# Teensy3_based_M_M_board.net
KiCad netlist of a schematic drawn in EAGLE
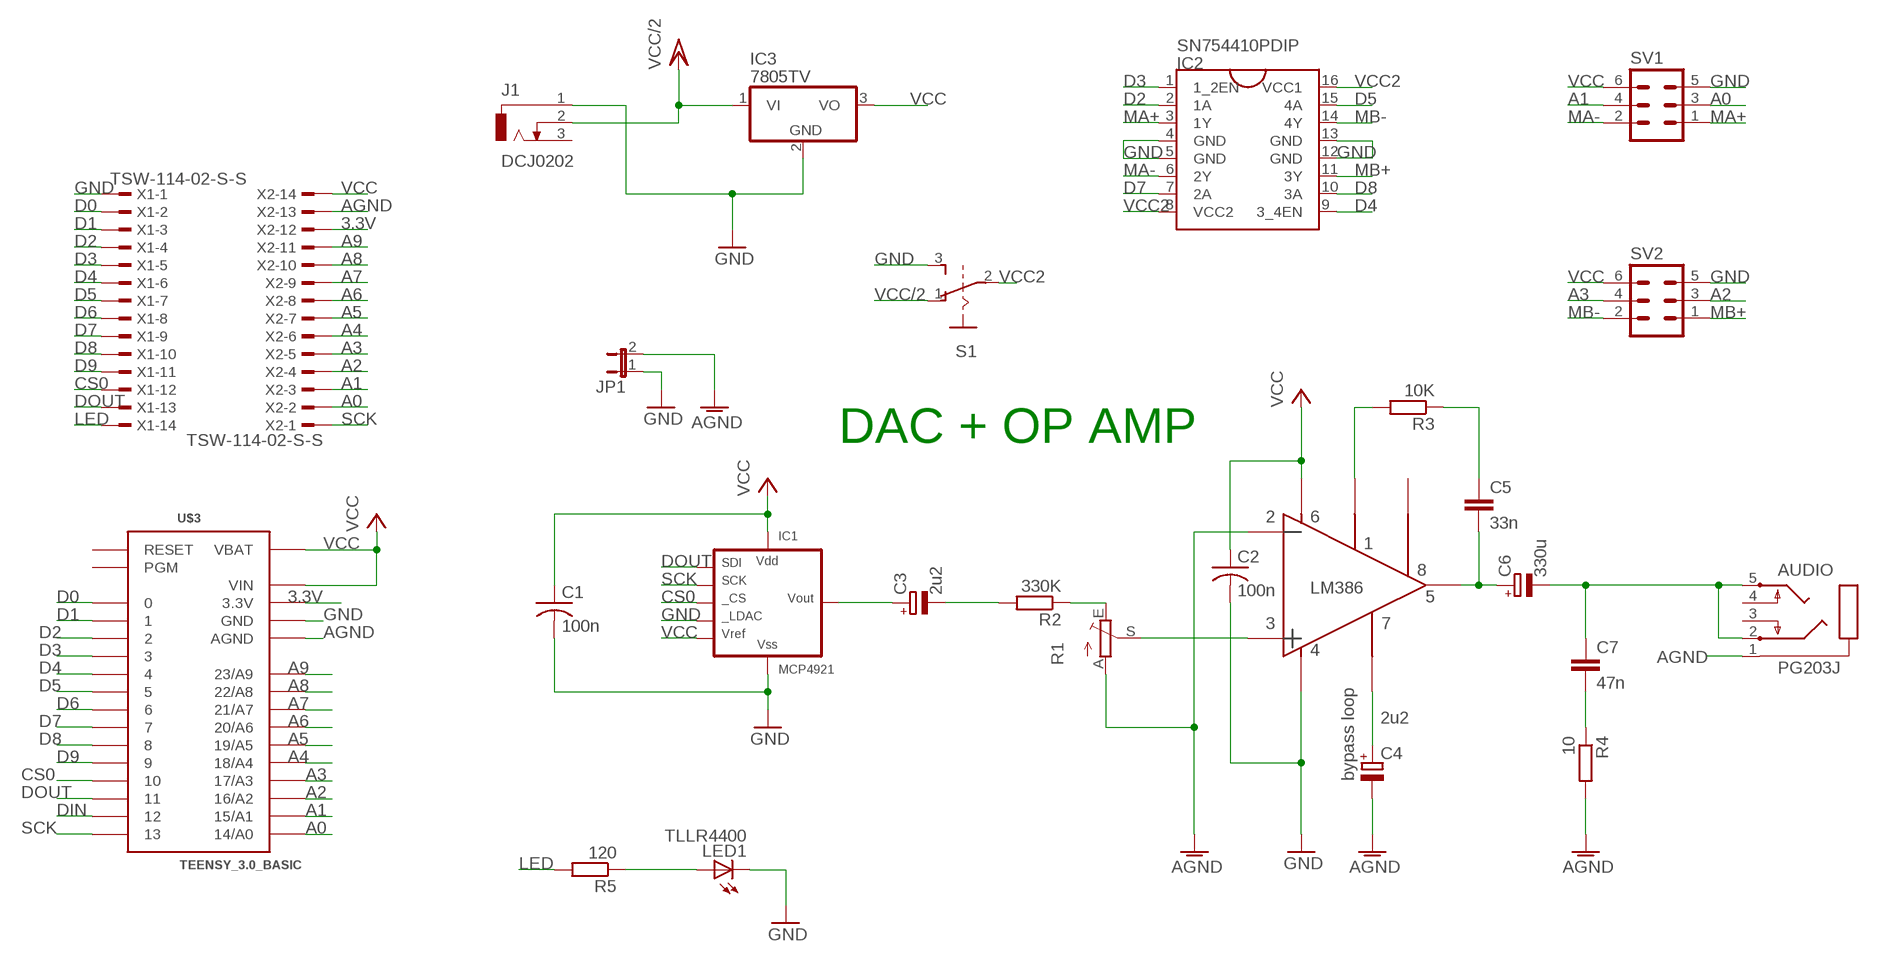
[diagram p0: schematic, sheet 1]

(export (version "E")
  (design (tool "Eeschema 10.0.6"))
  (components
    (comp (ref "AUDIO")
      (value "PG203J")
      (footprint "eagle-import:PG203J")
      (libsource (lib "eagle-import") (part "PG203J"))
    )
    (comp (ref "C1")
      (value "100n")
      (footprint "eagle-import:C050-035X075")
      (libsource (lib "eagle-import") (part "C-US050-035X075"))
    )
    (comp (ref "C2")
      (value "100n")
      (footprint "eagle-import:C050-035X075")
      (libsource (lib "eagle-import") (part "C-US050-035X075"))
    )
    (comp (ref "C3")
      (value "2u2")
      (footprint "eagle-import:E2-5")
      (libsource (lib "eagle-import") (part "CPOL-EUE2-5"))
    )
    (comp (ref "C4")
      (value "2u2")
      (footprint "eagle-import:E2-5")
      (libsource (lib "eagle-import") (part "CPOL-EUE2-5"))
    )
    (comp (ref "C5")
      (value "33n")
      (footprint "eagle-import:C050-024X044")
      (libsource (lib "eagle-import") (part "C-EU050-024X044"))
    )
    (comp (ref "C6")
      (value "330u")
      (footprint "eagle-import:E2,5-7")
      (libsource (lib "eagle-import") (part "CPOL-EUE2.5-7"))
    )
    (comp (ref "C7")
      (value "47n")
      (footprint "eagle-import:C050-024X044")
      (libsource (lib "eagle-import") (part "C-EU050-024X044"))
    )
    (comp (ref "IC1")
      (value "MCP4921")
      (footprint "eagle-import:DIL8")
      (libsource (lib "eagle-import") (part "MCP4921P"))
    )
    (comp (ref "IC2")
      (value "SN754410PDIP")
      (footprint "eagle-import:DIL16")
      (libsource (lib "eagle-import") (part "SN754410PDIP"))
    )
    (comp (ref "IC3")
      (value "7805TV")
      (footprint "eagle-import:TO220V")
      (libsource (lib "eagle-import") (part "78TV05"))
    )
    (comp (ref "J1")
      (value "DCJ0202")
      (footprint "eagle-import:DCJ0202")
      (libsource (lib "eagle-import") (part "DCJ0202"))
    )
    (comp (ref "JP1")
      (value "JP1E")
      (footprint "eagle-import:JP1")
      (libsource (lib "eagle-import") (part "JP1E"))
    )
    (comp (ref "LED1")
      (value "TLLR4400")
      (footprint "eagle-import:LED3MM")
      (fields (field (name "MF") "VISHAY SEMICONDUCTOR"))
      (libsource (lib "eagle-import") (part "TLLR4400"))
    )
    (comp (ref "R1")
      (value "TRIM_EU-CA9V")
      (footprint "eagle-import:CA9V")
      (libsource (lib "eagle-import") (part "TRIM_EU-CA9V"))
    )
    (comp (ref "R2")
      (value "330K")
      (footprint "eagle-import:0207_10")
      (libsource (lib "eagle-import") (part "R-EU_0207/10"))
    )
    (comp (ref "R3")
      (value "10K")
      (footprint "eagle-import:0207_10")
      (libsource (lib "eagle-import") (part "R-EU_0207/10"))
    )
    (comp (ref "R4")
      (value "10")
      (footprint "eagle-import:0207_10")
      (libsource (lib "eagle-import") (part "R-EU_0207/10"))
    )
    (comp (ref "R5")
      (value "120")
      (footprint "eagle-import:0207_10")
      (libsource (lib "eagle-import") (part "R-EU_0207/10"))
    )
    (comp (ref "S1")
      (value "EG1218")
      (footprint "eagle-import:GF-126-0159")
      (libsource (lib "eagle-import") (part "EG1218"))
    )
    (comp (ref "SV1")
      (value "ML6")
      (footprint "eagle-import:ML6")
      (libsource (lib "eagle-import") (part "ML6"))
    )
    (comp (ref "SV2")
      (value "ML6")
      (footprint "eagle-import:ML6")
      (libsource (lib "eagle-import") (part "ML6"))
    )
    (comp (ref "U$2")
      (value "LM386")
      (footprint "eagle-import:LM386")
      (libsource (lib "eagle-import") (part "LM386OA"))
    )
    (comp (ref "U$3")
      (value "TEENSY_3.0_BASIC")
      (footprint "eagle-import:TEENSY_3.0_BASIC")
      (libsource (lib "eagle-import") (part "TEENSY_3.0_BASIC"))
    )
    (comp (ref "X1")
      (value "TSW-114-02-S-S")
      (footprint "eagle-import:TSW-114-02-S-S")
      (libsource (lib "eagle-import") (part "TSW-114-02-S-S"))
    )
    (comp (ref "X2")
      (value "TSW-114-02-S-S")
      (footprint "eagle-import:TSW-114-02-S-S")
      (libsource (lib "eagle-import") (part "TSW-114-02-S-S"))
    )
  )
  (nets
    (net (code "1") (name "/3.3V") (class "Default")
      (node (ref "U$3") (pin "3.3V") (pinfunction "3.3V_3.3V") (pintype "power_in"))
      (node (ref "U$3") (pin "3.3V1") (pinfunction "3.3V_3.3V1") (pintype "power_in"))
      (node (ref "X2") (pin "12") (pinfunction "1_12") (pintype "passive"))
    )
    (net (code "2") (name "/A0") (class "Default")
      (node (ref "SV1") (pin "3") (pinfunction "3_3") (pintype "passive"))
      (node (ref "U$3") (pin "14/A0") (pinfunction "14/A0_14/A0") (pintype "bidirectional"))
      (node (ref "X2") (pin "2") (pinfunction "1_2") (pintype "passive"))
    )
    (net (code "3") (name "/A1") (class "Default")
      (node (ref "SV1") (pin "4") (pinfunction "4_4") (pintype "passive"))
      (node (ref "U$3") (pin "15/A1") (pinfunction "15/A1_15/A1") (pintype "bidirectional"))
      (node (ref "X2") (pin "3") (pinfunction "1_3") (pintype "passive"))
    )
    (net (code "4") (name "/A2") (class "Default")
      (node (ref "SV2") (pin "3") (pinfunction "3_3") (pintype "passive"))
      (node (ref "U$3") (pin "16/A2") (pinfunction "16/A2_16/A2") (pintype "bidirectional"))
      (node (ref "X2") (pin "4") (pinfunction "1_4") (pintype "passive"))
    )
    (net (code "5") (name "/A3") (class "Default")
      (node (ref "SV2") (pin "4") (pinfunction "4_4") (pintype "passive"))
      (node (ref "U$3") (pin "17/A3") (pinfunction "17/A3_17/A3") (pintype "bidirectional"))
      (node (ref "X2") (pin "5") (pinfunction "1_5") (pintype "passive"))
    )
    (net (code "6") (name "/A4") (class "Default")
      (node (ref "U$3") (pin "18/A4") (pinfunction "18/A4_18/A4") (pintype "bidirectional"))
      (node (ref "X2") (pin "6") (pinfunction "1_6") (pintype "passive"))
    )
    (net (code "7") (name "/A5") (class "Default")
      (node (ref "U$3") (pin "19/A5") (pinfunction "19/A5_19/A5") (pintype "bidirectional"))
      (node (ref "X2") (pin "7") (pinfunction "1_7") (pintype "passive"))
    )
    (net (code "8") (name "/A6") (class "Default")
      (node (ref "U$3") (pin "20/A6") (pinfunction "20/A6_20/A6") (pintype "bidirectional"))
      (node (ref "X2") (pin "8") (pinfunction "1_8") (pintype "passive"))
    )
    (net (code "9") (name "/A7") (class "Default")
      (node (ref "U$3") (pin "21/A7") (pinfunction "21/A7_21/A7") (pintype "bidirectional"))
      (node (ref "X2") (pin "9") (pinfunction "1_9") (pintype "passive"))
    )
    (net (code "10") (name "/A8") (class "Default")
      (node (ref "U$3") (pin "22/A8") (pinfunction "22/A8_22/A8") (pintype "bidirectional"))
      (node (ref "X2") (pin "10") (pinfunction "1_10") (pintype "passive"))
    )
    (net (code "11") (name "/A9") (class "Default")
      (node (ref "U$3") (pin "23/A9") (pinfunction "23/A9_23/A9") (pintype "bidirectional"))
      (node (ref "X2") (pin "11") (pinfunction "1_11") (pintype "passive"))
    )
    (net (code "12") (name "/CS0") (class "Default")
      (node (ref "IC1") (pin "2") (pinfunction "CS_2") (pintype "input"))
      (node (ref "U$3") (pin "10") (pinfunction "10_10") (pintype "bidirectional"))
      (node (ref "X1") (pin "12") (pinfunction "1_12") (pintype "passive"))
    )
    (net (code "13") (name "/D0") (class "Default")
      (node (ref "U$3") (pin "0") (pinfunction "0_0") (pintype "bidirectional"))
      (node (ref "X1") (pin "2") (pinfunction "1_2") (pintype "passive"))
    )
    (net (code "14") (name "/D1") (class "Default")
      (node (ref "U$3") (pin "1") (pinfunction "1_1") (pintype "bidirectional"))
      (node (ref "X1") (pin "3") (pinfunction "1_3") (pintype "passive"))
    )
    (net (code "15") (name "/D2") (class "Default")
      (node (ref "IC2") (pin "2") (pinfunction "1A_2") (pintype "bidirectional"))
      (node (ref "U$3") (pin "2") (pinfunction "2_2") (pintype "bidirectional"))
      (node (ref "X1") (pin "4") (pinfunction "1_4") (pintype "passive"))
    )
    (net (code "16") (name "/D3") (class "Default")
      (node (ref "IC2") (pin "1") (pinfunction "1_2EN_1") (pintype "bidirectional"))
      (node (ref "U$3") (pin "3") (pinfunction "3_3") (pintype "bidirectional"))
      (node (ref "X1") (pin "5") (pinfunction "1_5") (pintype "passive"))
    )
    (net (code "17") (name "/D4") (class "Default")
      (node (ref "IC2") (pin "9") (pinfunction "3_4EN_9") (pintype "bidirectional"))
      (node (ref "U$3") (pin "4") (pinfunction "4_4") (pintype "bidirectional"))
      (node (ref "X1") (pin "6") (pinfunction "1_6") (pintype "passive"))
    )
    (net (code "18") (name "/D5") (class "Default")
      (node (ref "IC2") (pin "15") (pinfunction "4A_15") (pintype "bidirectional"))
      (node (ref "U$3") (pin "5") (pinfunction "5_5") (pintype "bidirectional"))
      (node (ref "X1") (pin "7") (pinfunction "1_7") (pintype "passive"))
    )
    (net (code "19") (name "/D6") (class "Default")
      (node (ref "U$3") (pin "6") (pinfunction "6_6") (pintype "bidirectional"))
      (node (ref "X1") (pin "8") (pinfunction "1_8") (pintype "passive"))
    )
    (net (code "20") (name "/D7") (class "Default")
      (node (ref "IC2") (pin "7") (pinfunction "2A_7") (pintype "bidirectional"))
      (node (ref "U$3") (pin "7") (pinfunction "7_7") (pintype "bidirectional"))
      (node (ref "X1") (pin "9") (pinfunction "1_9") (pintype "passive"))
    )
    (net (code "21") (name "/D8") (class "Default")
      (node (ref "IC2") (pin "10") (pinfunction "3A_10") (pintype "bidirectional"))
      (node (ref "U$3") (pin "8") (pinfunction "8_8") (pintype "bidirectional"))
      (node (ref "X1") (pin "10") (pinfunction "1_10") (pintype "passive"))
    )
    (net (code "22") (name "/D9") (class "Default")
      (node (ref "U$3") (pin "9") (pinfunction "9_9") (pintype "bidirectional"))
      (node (ref "X1") (pin "11") (pinfunction "1_11") (pintype "passive"))
    )
    (net (code "23") (name "/DIN") (class "Default")
      (node (ref "U$3") (pin "12") (pinfunction "12_12") (pintype "bidirectional"))
    )
    (net (code "24") (name "/DOUT") (class "Default")
      (node (ref "IC1") (pin "4") (pinfunction "SDI_4") (pintype "input"))
      (node (ref "U$3") (pin "11") (pinfunction "11_11") (pintype "bidirectional"))
      (node (ref "X1") (pin "13") (pinfunction "1_13") (pintype "passive"))
    )
    (net (code "25") (name "/LED") (class "Default")
      (node (ref "R5") (pin "2") (pinfunction "2_2") (pintype "passive"))
      (node (ref "X1") (pin "14") (pinfunction "1_14") (pintype "passive"))
    )
    (net (code "26") (name "/MA+") (class "Default")
      (node (ref "IC2") (pin "3") (pinfunction "1Y_3") (pintype "bidirectional"))
      (node (ref "SV1") (pin "1") (pinfunction "1_1") (pintype "passive"))
    )
    (net (code "27") (name "/MA-") (class "Default")
      (node (ref "IC2") (pin "6") (pinfunction "2Y_6") (pintype "bidirectional"))
      (node (ref "SV1") (pin "2") (pinfunction "2_2") (pintype "passive"))
    )
    (net (code "28") (name "/MB+") (class "Default")
      (node (ref "IC2") (pin "11") (pinfunction "3Y_11") (pintype "bidirectional"))
      (node (ref "SV2") (pin "1") (pinfunction "1_1") (pintype "passive"))
    )
    (net (code "29") (name "/MB-") (class "Default")
      (node (ref "IC2") (pin "14") (pinfunction "4Y_14") (pintype "bidirectional"))
      (node (ref "SV2") (pin "2") (pinfunction "2_2") (pintype "passive"))
    )
    (net (code "30") (name "/SCK") (class "Default")
      (node (ref "IC1") (pin "3") (pinfunction "SCK_3") (pintype "input"))
      (node (ref "U$3") (pin "13") (pinfunction "13_13") (pintype "bidirectional"))
      (node (ref "X2") (pin "1") (pinfunction "1_1") (pintype "passive"))
    )
    (net (code "31") (name "/VCC2") (class "Default")
      (node (ref "IC2") (pin "16") (pinfunction "VCC1_16") (pintype "bidirectional"))
      (node (ref "IC2") (pin "8") (pinfunction "VCC2_8") (pintype "bidirectional"))
      (node (ref "S1") (pin "2") (pinfunction "02_2") (pintype "passive"))
    )
    (net (code "32") (name "AGND") (class "Default")
      (node (ref "AUDIO") (pin "1") (pinfunction "1_1") (pintype "passive"))
      (node (ref "C4") (pin "-") (pinfunction "-_-") (pintype "passive"))
      (node (ref "JP1") (pin "2") (pinfunction "2_2") (pintype "passive"))
      (node (ref "R1") (pin "A") (pinfunction "A_A") (pintype "passive"))
      (node (ref "R4") (pin "2") (pinfunction "2_2") (pintype "passive"))
      (node (ref "U$2") (pin "2") (pinfunction "P$2_2") (pintype "bidirectional"))
      (node (ref "U$3") (pin "AGND") (pinfunction "AGND_AGND") (pintype "power_in"))
      (node (ref "X2") (pin "13") (pinfunction "1_13") (pintype "passive"))
    )
    (net (code "33") (name "GND") (class "Default")
      (node (ref "C1") (pin "2") (pinfunction "2_2") (pintype "passive"))
      (node (ref "C2") (pin "2") (pinfunction "2_2") (pintype "passive"))
      (node (ref "IC1") (pin "5") (pinfunction "LDAC_5") (pintype "input"))
      (node (ref "IC1") (pin "7") (pinfunction "VSS_7") (pintype "power_in"))
      (node (ref "IC2") (pin "12") (pinfunction "GND_12") (pintype "bidirectional"))
      (node (ref "IC2") (pin "13") (pinfunction "GND_13") (pintype "bidirectional"))
      (node (ref "IC2") (pin "4") (pinfunction "GND_4") (pintype "bidirectional"))
      (node (ref "IC2") (pin "5") (pinfunction "GND_5") (pintype "bidirectional"))
      (node (ref "IC3") (pin "2") (pinfunction "GND_2") (pintype "passive"))
      (node (ref "J1") (pin "1") (pinfunction "1_1") (pintype "passive"))
      (node (ref "JP1") (pin "1") (pinfunction "1_1") (pintype "passive"))
      (node (ref "LED1") (pin "K") (pinfunction "C_K") (pintype "passive"))
      (node (ref "S1") (pin "3") (pinfunction "3_3") (pintype "passive"))
      (node (ref "SV1") (pin "5") (pinfunction "5_5") (pintype "passive"))
      (node (ref "SV2") (pin "5") (pinfunction "5_5") (pintype "passive"))
      (node (ref "U$2") (pin "4") (pinfunction "P$4_4") (pintype "bidirectional"))
      (node (ref "U$3") (pin "GND") (pinfunction "GND_GND") (pintype "power_in"))
      (node (ref "U$3") (pin "GND1") (pinfunction "GND_GND1") (pintype "power_in"))
      (node (ref "X1") (pin "1") (pinfunction "1_1") (pintype "passive"))
    )
    (net (code "34") (name "Net-(AUDIO-Pad2)") (class "Default")
      (node (ref "AUDIO") (pin "2") (pinfunction "2_2") (pintype "passive"))
      (node (ref "AUDIO") (pin "5") (pinfunction "5_5") (pintype "passive"))
      (node (ref "C6") (pin "-") (pinfunction "-_-") (pintype "passive"))
      (node (ref "C7") (pin "1") (pinfunction "1_1") (pintype "passive"))
    )
    (net (code "35") (name "Net-(C3-Pad-)") (class "Default")
      (node (ref "C3") (pin "-") (pinfunction "-_-") (pintype "passive"))
      (node (ref "R2") (pin "2") (pinfunction "2_2") (pintype "passive"))
    )
    (net (code "36") (name "Net-(C5-Pad1)") (class "Default")
      (node (ref "C5") (pin "1") (pinfunction "1_1") (pintype "passive"))
      (node (ref "R3") (pin "1") (pinfunction "1_1") (pintype "passive"))
    )
    (net (code "37") (name "Net-(C7-Pad2)") (class "Default")
      (node (ref "C7") (pin "2") (pinfunction "2_2") (pintype "passive"))
      (node (ref "R4") (pin "1") (pinfunction "1_1") (pintype "passive"))
    )
    (net (code "38") (name "Net-(IC1-VOUT)") (class "Default")
      (node (ref "C3") (pin "+") (pinfunction "+_+") (pintype "passive"))
      (node (ref "IC1") (pin "8") (pinfunction "VOUT_8") (pintype "output"))
    )
    (net (code "39") (name "Net-(LED1-PadA)") (class "Default")
      (node (ref "LED1") (pin "A") (pinfunction "A_A") (pintype "passive"))
      (node (ref "R5") (pin "1") (pinfunction "1_1") (pintype "passive"))
    )
    (net (code "40") (name "Net-(R1-PadE)") (class "Default")
      (node (ref "R1") (pin "E") (pinfunction "E_E") (pintype "passive"))
      (node (ref "R2") (pin "1") (pinfunction "1_1") (pintype "passive"))
    )
    (net (code "41") (name "Net-(U$2-P$1)") (class "Default")
      (node (ref "R3") (pin "2") (pinfunction "2_2") (pintype "passive"))
      (node (ref "U$2") (pin "1") (pinfunction "P$1_1") (pintype "bidirectional"))
    )
    (net (code "42") (name "Net-(U$2-P$3)") (class "Default")
      (node (ref "R1") (pin "S") (pinfunction "S_S") (pintype "passive"))
      (node (ref "U$2") (pin "3") (pinfunction "P$3_3") (pintype "bidirectional"))
    )
    (net (code "43") (name "Net-(U$2-P$5)") (class "Default")
      (node (ref "C5") (pin "2") (pinfunction "2_2") (pintype "passive"))
      (node (ref "C6") (pin "+") (pinfunction "+_+") (pintype "passive"))
      (node (ref "U$2") (pin "5") (pinfunction "P$5_5") (pintype "bidirectional"))
    )
    (net (code "44") (name "Net-(U$2-P$7)") (class "Default")
      (node (ref "C4") (pin "+") (pinfunction "+_+") (pintype "passive"))
      (node (ref "U$2") (pin "7") (pinfunction "P$7_7") (pintype "bidirectional"))
    )
    (net (code "45") (name "VCC") (class "Default")
      (node (ref "C1") (pin "1") (pinfunction "1_1") (pintype "passive"))
      (node (ref "C2") (pin "1") (pinfunction "1_1") (pintype "passive"))
      (node (ref "IC1") (pin "1") (pinfunction "VDD_1") (pintype "power_in"))
      (node (ref "IC1") (pin "6") (pinfunction "VREF_6") (pintype "input"))
      (node (ref "IC3") (pin "3") (pinfunction "VO_3") (pintype "passive"))
      (node (ref "SV1") (pin "6") (pinfunction "6_6") (pintype "passive"))
      (node (ref "SV2") (pin "6") (pinfunction "6_6") (pintype "passive"))
      (node (ref "U$2") (pin "6") (pinfunction "P$6_6") (pintype "bidirectional"))
      (node (ref "U$3") (pin "VBAT") (pinfunction "VBAT_VBAT") (pintype "power_in"))
      (node (ref "U$3") (pin "VIN") (pinfunction "VIN_VIN") (pintype "power_in"))
      (node (ref "X2") (pin "14") (pinfunction "1_14") (pintype "passive"))
    )
    (net (code "46") (name "VCC{slash}2") (class "Default")
      (node (ref "IC3") (pin "1") (pinfunction "VI_1") (pintype "input"))
      (node (ref "J1") (pin "2") (pinfunction "2_2") (pintype "passive"))
      (node (ref "S1") (pin "1") (pinfunction "1_1") (pintype "passive"))
    )
    (net (code "47") (name "unconnected-(AUDIO-Pad3)") (class "Default")
      (node (ref "AUDIO") (pin "3") (pinfunction "3_3") (pintype "passive"))
    )
    (net (code "48") (name "unconnected-(AUDIO-Pad4)") (class "Default")
      (node (ref "AUDIO") (pin "4") (pinfunction "4_4") (pintype "passive"))
    )
    (net (code "49") (name "unconnected-(J1-Pad3)") (class "Default")
      (node (ref "J1") (pin "3") (pinfunction "3_3") (pintype "passive"))
    )
    (net (code "50") (name "unconnected-(U$2-P$8-Pad8)") (class "Default")
      (node (ref "U$2") (pin "8") (pinfunction "P$8_8") (pintype "bidirectional"))
    )
    (net (code "51") (name "unconnected-(U$3-PadPGM)") (class "Default")
      (node (ref "U$3") (pin "PGM") (pinfunction "PGM_PGM") (pintype "bidirectional"))
    )
    (net (code "52") (name "unconnected-(U$3-PadRESET)") (class "Default")
      (node (ref "U$3") (pin "RESET") (pinfunction "RESET_RESET") (pintype "bidirectional"))
    )
  )
)
